# dome-pcb.net
KiCad netlist of a schematic drawn in EAGLE
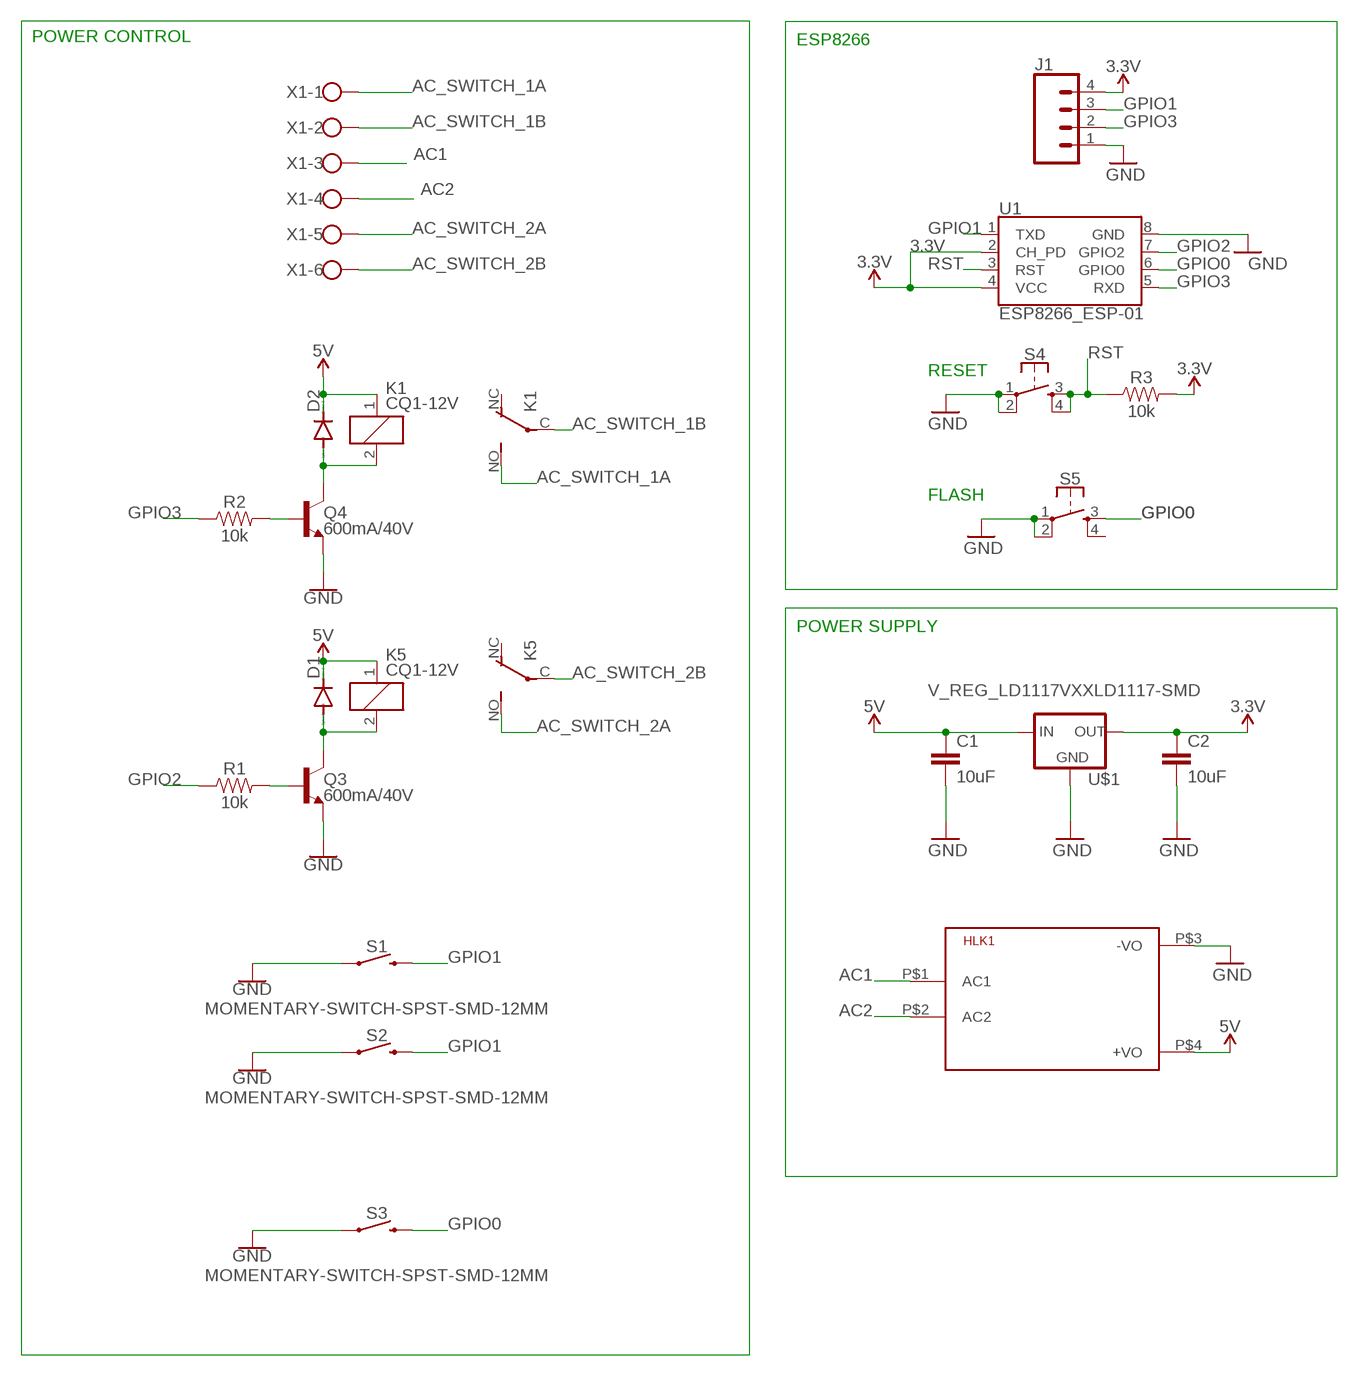
[diagram p0: schematic, sheet 1]

(export (version "E")
  (design (tool "Eeschema 10.0.6"))
  (components
    (comp (ref "C1")
      (value "10uF")
      (footprint "eagle-import:0603")
      (libsource (lib "eagle-import") (part "10UF-0603-6.3V-20%"))
    )
    (comp (ref "C2")
      (value "10uF")
      (footprint "eagle-import:0603")
      (libsource (lib "eagle-import") (part "10UF-0603-6.3V-20%"))
    )
    (comp (ref "D1")
      (value "DIODE-DO-214AC")
      (footprint "eagle-import:DO-214AC")
      (libsource (lib "eagle-import") (part "DIODE-DO-214AC"))
    )
    (comp (ref "D2")
      (value "DIODE-DO-214AC")
      (footprint "eagle-import:DO-214AC")
      (libsource (lib "eagle-import") (part "DIODE-DO-214AC"))
    )
    (comp (ref "HLK1")
      (value "HLK-PM013W")
      (footprint "eagle-import:HLK-PM01")
      (libsource (lib "eagle-import") (part "HLK-PM013W"))
    )
    (comp (ref "J1")
      (value "CONN_04PTH")
      (footprint "eagle-import:1X04")
      (libsource (lib "eagle-import") (part "CONN_04PTH"))
    )
    (comp (ref "K1")
      (value "CQ1-12V")
      (footprint "eagle-import:CQ1")
      (libsource (lib "eagle-import") (part "CQ1-12V"))
    )
    (comp (ref "K5")
      (value "CQ1-12V")
      (footprint "eagle-import:CQ1")
      (libsource (lib "eagle-import") (part "CQ1-12V"))
    )
    (comp (ref "Q3")
      (value "600mA/40V")
      (footprint "eagle-import:SOT23-3")
      (libsource (lib "eagle-import") (part "TRANS_NPN-MMBT2222AL"))
    )
    (comp (ref "Q4")
      (value "600mA/40V")
      (footprint "eagle-import:SOT23-3")
      (libsource (lib "eagle-import") (part "TRANS_NPN-MMBT2222AL"))
    )
    (comp (ref "R1")
      (value "10k")
      (footprint "eagle-import:0603")
      (libsource (lib "eagle-import") (part "10KOHM-0603-1/10W-1%"))
    )
    (comp (ref "R2")
      (value "10k")
      (footprint "eagle-import:0603")
      (libsource (lib "eagle-import") (part "10KOHM-0603-1/10W-1%"))
    )
    (comp (ref "R3")
      (value "10k")
      (footprint "eagle-import:0603")
      (libsource (lib "eagle-import") (part "10KOHM-0603-1/10W-1%"))
    )
    (comp (ref "S1")
      (value "MOMENTARY-SWITCH-SPST-SMD-12MM")
      (footprint "eagle-import:TACTILE_SWITCH_SMD_12MM")
      (libsource (lib "eagle-import") (part "MOMENTARY-SWITCH-SPST-SMD-12MM"))
    )
    (comp (ref "S2")
      (value "MOMENTARY-SWITCH-SPST-SMD-12MM")
      (footprint "eagle-import:TACTILE_SWITCH_SMD_12MM")
      (libsource (lib "eagle-import") (part "MOMENTARY-SWITCH-SPST-SMD-12MM"))
    )
    (comp (ref "S3")
      (value "MOMENTARY-SWITCH-SPST-SMD-12MM")
      (footprint "eagle-import:TACTILE_SWITCH_SMD_12MM")
      (libsource (lib "eagle-import") (part "MOMENTARY-SWITCH-SPST-SMD-12MM"))
    )
    (comp (ref "S4")
      (value "MOMENTARY-SWITCH-SPST-2-SMD-5.2MM")
      (footprint "eagle-import:TACTILE_SWITCH_SMD_5.2MM")
      (libsource (lib "eagle-import") (part "MOMENTARY-SWITCH-SPST-2-SMD-5.2MM"))
    )
    (comp (ref "S5")
      (value "MOMENTARY-SWITCH-SPST-2-SMD-5.2MM")
      (footprint "eagle-import:TACTILE_SWITCH_SMD_5.2MM")
      (libsource (lib "eagle-import") (part "MOMENTARY-SWITCH-SPST-2-SMD-5.2MM"))
    )
    (comp (ref "U$1")
      (value "V_REG_LD1117VXXLD1117-SMD")
      (footprint "eagle-import:SOT223")
      (libsource (lib "eagle-import") (part "V_REG_LD1117VXXLD1117-SMD"))
    )
    (comp (ref "U1")
      (value "ESP8266_ESP-01")
      (footprint "eagle-import:ESP8266_ESP-01")
      (libsource (lib "eagle-import") (part "ESP8266_ESP-01"))
    )
    (comp (ref "X1")
      (value "W237-6")
      (footprint "eagle-import:W237-6")
      (libsource (lib "eagle-import") (part "W237-6"))
    )
  )
  (nets
    (net (code "1") (name "/AC1") (class "Default")
      (node (ref "HLK1") (pin "P$1") (pinfunction "AC1_P$1") (pintype "bidirectional"))
      (node (ref "X1") (pin "3") (pinfunction "KL_3") (pintype "passive"))
    )
    (net (code "2") (name "/AC2") (class "Default")
      (node (ref "HLK1") (pin "P$2") (pinfunction "AC2_P$2") (pintype "bidirectional"))
      (node (ref "X1") (pin "4") (pinfunction "KL_4") (pintype "passive"))
    )
    (net (code "3") (name "/AC_SWITCH_1A") (class "Default")
      (node (ref "K1") (pin "NO") (pinfunction "S_NO") (pintype "passive"))
      (node (ref "X1") (pin "1") (pinfunction "KL_1") (pintype "passive"))
    )
    (net (code "4") (name "/AC_SWITCH_1B") (class "Default")
      (node (ref "K1") (pin "C") (pinfunction "P_C") (pintype "passive"))
      (node (ref "X1") (pin "2") (pinfunction "KL_2") (pintype "passive"))
    )
    (net (code "5") (name "/AC_SWITCH_2A") (class "Default")
      (node (ref "K5") (pin "NO") (pinfunction "S_NO") (pintype "passive"))
      (node (ref "X1") (pin "5") (pinfunction "KL_5") (pintype "passive"))
    )
    (net (code "6") (name "/AC_SWITCH_2B") (class "Default")
      (node (ref "K5") (pin "C") (pinfunction "P_C") (pintype "passive"))
      (node (ref "X1") (pin "6") (pinfunction "KL_6") (pintype "passive"))
    )
    (net (code "7") (name "/GPIO0") (class "Default")
      (node (ref "S3") (pin "3") (pinfunction "2_3") (pintype "passive"))
      (node (ref "S5") (pin "3") (pinfunction "3_3") (pintype "passive"))
      (node (ref "U1") (pin "6") (pinfunction "GPIO0_6") (pintype "bidirectional"))
    )
    (net (code "8") (name "/GPIO1") (class "Default")
      (node (ref "J1") (pin "3") (pinfunction "3_3") (pintype "passive"))
      (node (ref "S1") (pin "3") (pinfunction "2_3") (pintype "passive"))
      (node (ref "S2") (pin "3") (pinfunction "2_3") (pintype "passive"))
      (node (ref "U1") (pin "1") (pinfunction "TXD_1") (pintype "bidirectional"))
    )
    (net (code "9") (name "/GPIO2") (class "Default")
      (node (ref "R1") (pin "1") (pinfunction "1_1") (pintype "passive"))
      (node (ref "U1") (pin "7") (pinfunction "GPIO2_7") (pintype "bidirectional"))
    )
    (net (code "10") (name "/GPIO3") (class "Default")
      (node (ref "J1") (pin "2") (pinfunction "2_2") (pintype "passive"))
      (node (ref "R2") (pin "1") (pinfunction "1_1") (pintype "passive"))
      (node (ref "U1") (pin "5") (pinfunction "RXD_5") (pintype "bidirectional"))
    )
    (net (code "11") (name "/RST") (class "Default")
      (node (ref "R3") (pin "1") (pinfunction "1_1") (pintype "passive"))
      (node (ref "S4") (pin "3") (pinfunction "3_3") (pintype "passive"))
      (node (ref "S4") (pin "4") (pinfunction "4_4") (pintype "passive"))
      (node (ref "U1") (pin "3") (pinfunction "RST_3") (pintype "bidirectional"))
    )
    (net (code "12") (name "3.3V") (class "Default")
      (node (ref "C2") (pin "1") (pinfunction "1_1") (pintype "passive"))
      (node (ref "J1") (pin "4") (pinfunction "4_4") (pintype "passive"))
      (node (ref "R3") (pin "2") (pinfunction "2_2") (pintype "passive"))
      (node (ref "U$1") (pin "2") (pinfunction "OUT_2") (pintype "passive"))
      (node (ref "U1") (pin "2") (pinfunction "CH_PD_2") (pintype "bidirectional"))
      (node (ref "U1") (pin "4") (pinfunction "VCC_4") (pintype "bidirectional"))
    )
    (net (code "13") (name "5V") (class "Default")
      (node (ref "C1") (pin "1") (pinfunction "1_1") (pintype "passive"))
      (node (ref "D1") (pin "C") (pinfunction "C_C") (pintype "passive"))
      (node (ref "D2") (pin "C") (pinfunction "C_C") (pintype "passive"))
      (node (ref "HLK1") (pin "P$4") (pinfunction "+VO_P$4") (pintype "bidirectional"))
      (node (ref "K1") (pin "1") (pinfunction "1_1") (pintype "passive"))
      (node (ref "K5") (pin "1") (pinfunction "1_1") (pintype "passive"))
      (node (ref "U$1") (pin "3") (pinfunction "IN_3") (pintype "input"))
    )
    (net (code "14") (name "GND") (class "Default")
      (node (ref "C1") (pin "2") (pinfunction "2_2") (pintype "passive"))
      (node (ref "C2") (pin "2") (pinfunction "2_2") (pintype "passive"))
      (node (ref "HLK1") (pin "P$3") (pinfunction "-VO_P$3") (pintype "bidirectional"))
      (node (ref "J1") (pin "1") (pinfunction "1_1") (pintype "passive"))
      (node (ref "Q3") (pin "2") (pinfunction "E_2") (pintype "passive"))
      (node (ref "Q4") (pin "2") (pinfunction "E_2") (pintype "passive"))
      (node (ref "S1") (pin "1") (pinfunction "1_1") (pintype "passive"))
      (node (ref "S2") (pin "1") (pinfunction "1_1") (pintype "passive"))
      (node (ref "S3") (pin "1") (pinfunction "1_1") (pintype "passive"))
      (node (ref "S4") (pin "1") (pinfunction "1_1") (pintype "passive"))
      (node (ref "S4") (pin "2") (pinfunction "2_2") (pintype "passive"))
      (node (ref "S5") (pin "1") (pinfunction "1_1") (pintype "passive"))
      (node (ref "S5") (pin "2") (pinfunction "2_2") (pintype "passive"))
      (node (ref "U$1") (pin "1") (pinfunction "GND_1") (pintype "input"))
      (node (ref "U1") (pin "8") (pinfunction "GND_8") (pintype "bidirectional"))
    )
    (net (code "15") (name "Net-(Q3-B)") (class "Default")
      (node (ref "Q3") (pin "1") (pinfunction "B_1") (pintype "passive"))
      (node (ref "R1") (pin "2") (pinfunction "2_2") (pintype "passive"))
    )
    (net (code "16") (name "Net-(Q3-C)") (class "Default")
      (node (ref "D1") (pin "A") (pinfunction "A_A") (pintype "passive"))
      (node (ref "K5") (pin "2") (pinfunction "2_2") (pintype "passive"))
      (node (ref "Q3") (pin "3") (pinfunction "C_3") (pintype "passive"))
    )
    (net (code "17") (name "Net-(Q4-B)") (class "Default")
      (node (ref "Q4") (pin "1") (pinfunction "B_1") (pintype "passive"))
      (node (ref "R2") (pin "2") (pinfunction "2_2") (pintype "passive"))
    )
    (net (code "18") (name "Net-(Q4-C)") (class "Default")
      (node (ref "D2") (pin "A") (pinfunction "A_A") (pintype "passive"))
      (node (ref "K1") (pin "2") (pinfunction "2_2") (pintype "passive"))
      (node (ref "Q4") (pin "3") (pinfunction "C_3") (pintype "passive"))
    )
    (net (code "19") (name "unconnected-(K1B-O-PadNC)") (class "Default")
      (node (ref "K1") (pin "NC") (pinfunction "O_NC") (pintype "passive"))
    )
    (net (code "20") (name "unconnected-(K5B-O-PadNC)") (class "Default")
      (node (ref "K5") (pin "NC") (pinfunction "O_NC") (pintype "passive"))
    )
    (net (code "21") (name "unconnected-(S5-Pad4)") (class "Default")
      (node (ref "S5") (pin "4") (pinfunction "4_4") (pintype "passive"))
    )
  )
)
